# 04_CPU02.net
KiCad netlist of a schematic drawn in Altium Designer
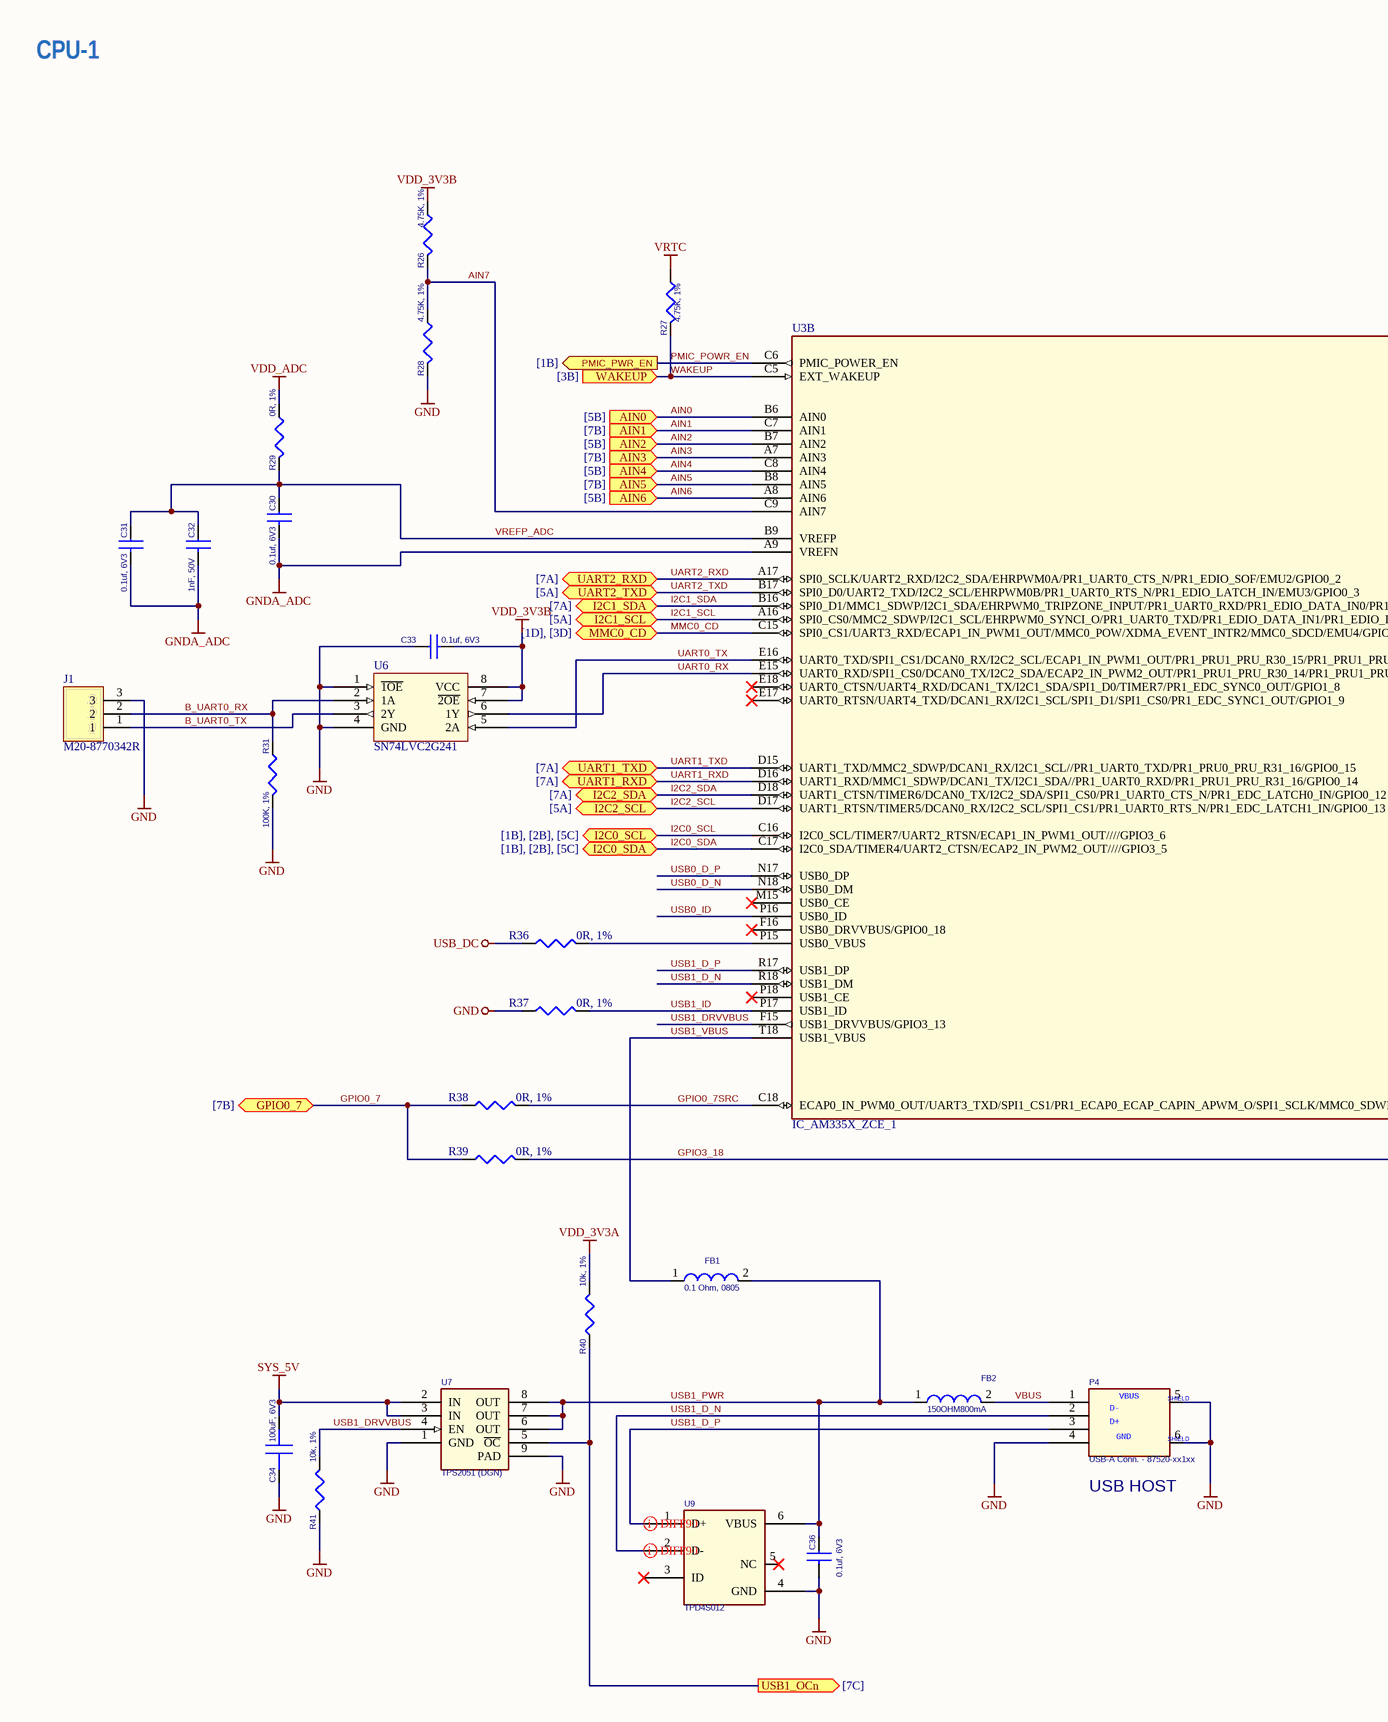
[diagram p0: 04_CPU02.SchDoc, left]
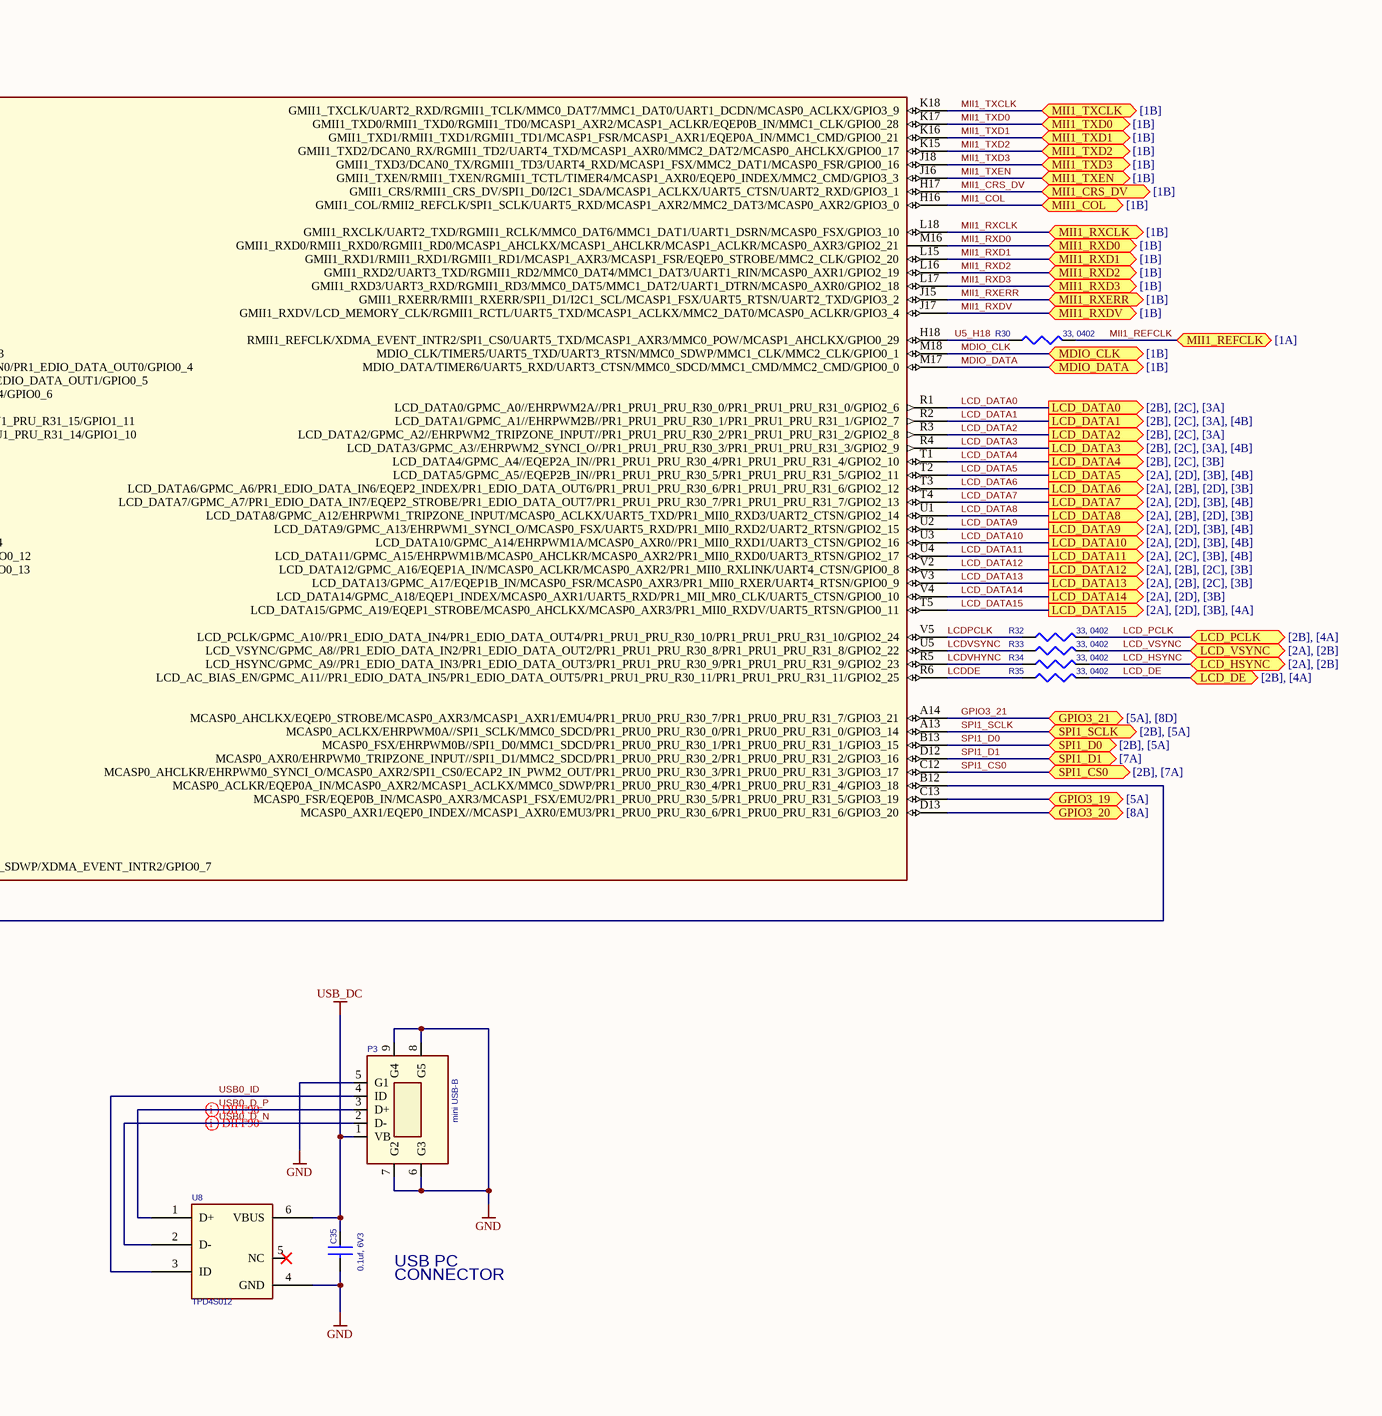
[diagram p1: 04_CPU02.SchDoc, right]

(export (version "E")
  (design (tool "Eeschema 10.0.6"))
  (components
    (comp (ref "C30")
      (value "0.1uf, 6V3")
      (footprint "402")
      (description "CAP CER 0.1UF 6.3V 10% X5R 0402")
      (fields
        (field (name "MANUFACTURER") "TDK Corporation")
        (field (name "MANUFACTURER PART NUMBER") "C1005X5R0J104K050BA")
      )
      (libsource (lib "BEAGLEBONEBLACK_REV A5B") (part "CAP_0.1uF_X7R_16V_10% 0402"))
    )
    (comp (ref "C31")
      (value "0.1uf, 6V3")
      (footprint "402")
      (description "CAP CER 0.1UF 6.3V 10% X5R 0402")
      (fields
        (field (name "MANUFACTURER") "TDK Corporation")
        (field (name "MANUFACTURER PART NUMBER") "C1005X5R0J104K050BA")
      )
      (libsource (lib "BEAGLEBONEBLACK_REV A5B") (part "CAP_0.1uF_X7R_16V_10% 0402"))
    )
    (comp (ref "C32")
      (value "1nF, 50V")
      (footprint "402")
      (description "CAP CER 1000PF 16V 10% X7R 0402")
      (fields
        (field (name "MANUFACTURER") "Yageo")
        (field (name "MANUFACTURER PART NUMBER") "CC0402KRX7R7BB102")
      )
      (libsource (lib "BEAGLEBONEBLACK_REV A5B") (part "CAP_0.001_X7R_50V_5%_0402"))
    )
    (comp (ref "C33")
      (value "0.1uf, 6V3")
      (footprint "402")
      (description "CAP CER 0.1UF 6.3V 10% X5R 0402")
      (fields
        (field (name "MANUFACTURER") "TDK Corporation")
        (field (name "MANUFACTURER PART NUMBER") "C1005X5R0J104K050BA")
      )
      (libsource (lib "BEAGLEBONEBLACK_REV A5B") (part "CAP_0.1uF_X7R_16V_10% 0402"))
    )
    (comp (ref "C34")
      (value "100uF, 6V3")
      (footprint "RD205SMD_250D")
      (description "CAP ALUM 100UF 6.3V 20% SMD")
      (fields
        (field (name "MANUFACTURER") "Cornell Dubilier Electronics (CDE)")
        (field (name "MANUFACTURER PART NUMBER") "AVE107M06D16T-F")
      )
      (libsource (lib "BEAGLEBONEBLACK_REV A5B") (part "CAP SMD"))
    )
    (comp (ref "C35")
      (value "0.1uf, 6V3")
      (footprint "402")
      (description "CAP CER 0.1UF 6.3V 10% X5R 0402")
      (fields
        (field (name "MANUFACTURER") "TDK Corporation")
        (field (name "MANUFACTURER PART NUMBER") "C1005X5R0J104K050BA")
      )
      (libsource (lib "BEAGLEBONEBLACK_REV A5B") (part "CAP_0.1uF_X7R_16V_10% 0402"))
    )
    (comp (ref "C36")
      (value "0.1uf, 6V3")
      (footprint "402")
      (description "CAP CER 0.1UF 6.3V 10% X5R 0402")
      (fields
        (field (name "MANUFACTURER") "TDK Corporation")
        (field (name "MANUFACTURER PART NUMBER") "C1005X5R0J104K050BA")
      )
      (libsource (lib "BEAGLEBONEBLACK_REV A5B") (part "CAP_0.1uF_X7R_16V_10% 0402"))
    )
    (comp (ref "FB1")
      (value "0.1 Ohm, 0805")
      (footprint "SM-7351-IND-0805")
      (description "RES .10 OHM 1/8W 5% 0805")
      (fields
        (field (name "MANUFACTURER") "CTS Resistor Products")
        (field (name "MANUFACTURER PART NUMBER") "73L3R10J")
      )
      (libsource (lib "BEAGLEBONEBLACK_REV A5B") (part "FER_180_200_0"))
    )
    (comp (ref "FB2")
      (value "150OHM800mA")
      (footprint "SM-7351-IND-0805")
      (description "FERRITE 800MA 150 OHM 0805 SMD")
      (fields (field (name "MFR") "Steward") (field (name "TIINTPARTNUMBER") "1L0010"))
      (libsource (lib "BEAGLEBONEBLACK_REV A5B") (part "FER_180_200_0"))
    )
    (comp (ref "J1")
      (value "M20-8770342R")
      (footprint "HARWIN_M20-8770342R")
      (description "Connector Header Surface Mount 3 position 0.100 (2.54mm)")
      (fields (field (name "MF") "Harwin Inc."))
      (libsource (lib "BEAGLEBONEBLACK_REV A5B_1") (part "M20-8770342R"))
    )
    (comp (ref "P3")
      (value "mini USB-B")
      (footprint "USB5MINI_4SHIELDED_SMD-5")
      (description "CONN RCPT USB MINI B R/A SMD")
      (fields (field (name "MANUFACTURER") "KYCON") (field (name "MANUFACTURER PART NUMBER") "0565790576"))
      (libsource (lib "BEAGLEBONEBLACK_REV A5B") (part "MINI-USB-AB-SOCKET"))
    )
    (comp (ref "P4")
      (value "USB-A Conn. - 87520-xx1xx")
      (description "CONN RCPT USB TYPE A R/A PCB")
      (fields (field (name "MANUFACTURER") "FCI") (field (name "MANUFACTURER PART NUMBER") "87520-0010BLF"))
      (libsource (lib "BEAGLEBONEBLACK_REV A5B") (part "CONN_54819-0578_2"))
    )
    (comp (ref "R26")
      (value "4.75K, 1%")
      (footprint "402")
      (description "RES 4.75K OHM 1/16W 1% 0402 SMD")
      (fields
        (field (name "MANUFACTURER") "Stackpole Electronics Inc")
        (field (name "MANUFACTURER PART NUMBER") "RMCF0402FT4K75")
      )
      (libsource (lib "BEAGLEBONEBLACK_REV A5B") (part "RES_4.75K_1/16W_1%_0402"))
    )
    (comp (ref "R27")
      (value "4.75K, 1%")
      (footprint "402")
      (description "RES 4.75K OHM 1/16W 1% 0402 SMD")
      (fields
        (field (name "MANUFACTURER") "Stackpole Electronics Inc")
        (field (name "MANUFACTURER PART NUMBER") "RMCF0402FT4K75")
      )
      (libsource (lib "BEAGLEBONEBLACK_REV A5B") (part "RES_4.75K_1/16W_1%_0402"))
    )
    (comp (ref "R28")
      (value "4.75K, 1%")
      (footprint "402")
      (description "RES 4.75K OHM 1/16W 1% 0402 SMD")
      (fields
        (field (name "MANUFACTURER") "Stackpole Electronics Inc")
        (field (name "MANUFACTURER PART NUMBER") "RMCF0402FT4K75")
      )
      (libsource (lib "BEAGLEBONEBLACK_REV A5B") (part "RES_4.75K_1/16W_1%_0402"))
    )
    (comp (ref "R29")
      (value "0R, 1%")
      (footprint "402")
      (description "RES 0.0 OHM 1/16W 0402 SMD")
      (fields
        (field (name "MANUFACTURER") "Yageo")
        (field (name "MANUFACTURER PART NUMBER") "RC0402JR-070RL")
      )
      (libsource (lib "BEAGLEBONEBLACK_REV A5B") (part "RES_0_1/16W_1%_0402"))
    )
    (comp (ref "R30")
      (value "33, 0402")
      (footprint "402")
      (description "RES 33 OHM 1/16W 5% 0402 SMD")
      (fields
        (field (name "MANUFACTURER") "Panasonic Electronic Components")
        (field (name "MANUFACTURER PART NUMBER") "ERJ-2GEJ330X")
      )
      (libsource (lib "BEAGLEBONEBLACK_REV A5B") (part "RES_33_0402"))
    )
    (comp (ref "R31")
      (value "100K, 1%")
      (footprint "402")
      (description "RES 100K OHM 1/16W 1% 0402 SMD")
      (fields
        (field (name "MANUFACTURER") "Stackpole Electronics Inc")
        (field (name "MANUFACTURER PART NUMBER") "RMCF0402FT100K")
      )
      (libsource (lib "BEAGLEBONEBLACK_REV A5B") (part "RES_100K_1/16W_1%_0402"))
    )
    (comp (ref "R32")
      (value "33, 0402")
      (footprint "402")
      (description "RES 33 OHM 1/16W 5% 0402 SMD")
      (fields
        (field (name "MANUFACTURER") "Panasonic Electronic Components")
        (field (name "MANUFACTURER PART NUMBER") "ERJ-2GEJ330X")
      )
      (libsource (lib "BEAGLEBONEBLACK_REV A5B") (part "RES_33_0402"))
    )
    (comp (ref "R33")
      (value "33, 0402")
      (footprint "402")
      (description "RES 33 OHM 1/16W 5% 0402 SMD")
      (fields
        (field (name "MANUFACTURER") "Panasonic Electronic Components")
        (field (name "MANUFACTURER PART NUMBER") "ERJ-2GEJ330X")
      )
      (libsource (lib "BEAGLEBONEBLACK_REV A5B") (part "RES_33_0402"))
    )
    (comp (ref "R34")
      (value "33, 0402")
      (footprint "402")
      (description "RES 33 OHM 1/16W 5% 0402 SMD")
      (fields
        (field (name "MANUFACTURER") "Panasonic Electronic Components")
        (field (name "MANUFACTURER PART NUMBER") "ERJ-2GEJ330X")
      )
      (libsource (lib "BEAGLEBONEBLACK_REV A5B") (part "RES_33_0402"))
    )
    (comp (ref "R35")
      (value "33, 0402")
      (footprint "402")
      (description "RES 33 OHM 1/16W 5% 0402 SMD")
      (fields
        (field (name "MANUFACTURER") "Panasonic Electronic Components")
        (field (name "MANUFACTURER PART NUMBER") "ERJ-2GEJ330X")
      )
      (libsource (lib "BEAGLEBONEBLACK_REV A5B") (part "RES_33_0402"))
    )
    (comp (ref "R36")
      (value "0R, 1%")
      (footprint "402")
      (description "RES 0.0 OHM 1/16W 0402 SMD")
      (fields
        (field (name "MANUFACTURER") "Yageo")
        (field (name "MANUFACTURER PART NUMBER") "RC0402JR-070RL")
      )
      (libsource (lib "BEAGLEBONEBLACK_REV A5B") (part "RES_0_1/16W_1%_0402"))
    )
    (comp (ref "R37")
      (value "0R, 1%")
      (footprint "402")
      (description "RES 0.0 OHM 1/16W 0402 SMD")
      (fields
        (field (name "MANUFACTURER") "Yageo")
        (field (name "MANUFACTURER PART NUMBER") "RC0402JR-070RL")
      )
      (libsource (lib "BEAGLEBONEBLACK_REV A5B") (part "RES_0_1/16W_1%_0402"))
    )
    (comp (ref "R38")
      (value "0R, 1%")
      (footprint "402")
      (description "RES 0.0 OHM 1/16W 0402 SMD")
      (fields
        (field (name "MANUFACTURER") "Yageo")
        (field (name "MANUFACTURER PART NUMBER") "RC0402JR-070RL")
      )
      (libsource (lib "BEAGLEBONEBLACK_REV A5B") (part "RES_0_1/16W_1%_0402"))
    )
    (comp (ref "R39")
      (value "0R, 1%")
      (footprint "402")
      (description "RES 0.0 OHM 1/16W 0402 SMD")
      (fields
        (field (name "MANUFACTURER") "Yageo")
        (field (name "MANUFACTURER PART NUMBER") "RC0402JR-070RL")
      )
      (libsource (lib "BEAGLEBONEBLACK_REV A5B") (part "RES_0_1/16W_1%_0402"))
    )
    (comp (ref "R40")
      (value "10k, 1%")
      (footprint "402")
      (description "RES 10K OHM 1/16W 5% 0402 SMD")
      (fields
        (field (name "MANUFACTURER") "Rohm Semiconductor")
        (field (name "MANUFACTURER PART NUMBER") "MCR01MZPJ103")
      )
      (libsource (lib "BEAGLEBONEBLACK_REV A5B") (part "RES SMD"))
    )
    (comp (ref "R41")
      (value "10k, 1%")
      (footprint "402")
      (description "RES 10K OHM 1/16W 5% 0402 SMD")
      (fields
        (field (name "MANUFACTURER") "Rohm Semiconductor")
        (field (name "MANUFACTURER PART NUMBER") "MCR01MZPJ103")
      )
      (libsource (lib "BEAGLEBONEBLACK_REV A5B") (part "RES SMD"))
    )
    (comp (ref "U3")
      (value "IC_AM335X_ZCE_1")
      (footprint "am33xx_15x15")
      (description "SubArctic Cortex A8 Processor 15x15")
      (fields
        (field (name "MANUFACTURER") "Texas Instruments")
        (field (name "MANUFACTURER PART NUMBER") "XAM3359ZCZ")
      )
      (libsource (lib "BEAGLEBONEBLACK_REV A5B_1") (part "IC_AM335X_ZCE_1"))
    )
    (comp (ref "U6")
      (value "SN74LVC2G241")
      (footprint "U_8_DCU")
      (description "IC BUFF/DVR TRI-ST DL 8VSSOP")
      (fields
        (field (name "MANUFACTURER") "Texas Instruments")
        (field (name "MANUFACTURER PART NUMBER") "SN74LVC2G241DCUR")
      )
      (libsource (lib "BEAGLEBONEBLACK_REV A5B") (part "SN74LVC2G241"))
    )
    (comp (ref "U7")
      (value "TPS2051 (DGN)")
      (description "IC 1.5A PWR DIST SWITCH 8-SOIC")
      (fields
        (field (name "MANUFACTURER") "Texas Instruments")
        (field (name "MANUFACTURER PART NUMBER") "TPS2051BDGNR")
      )
      (libsource (lib "BEAGLEBONEBLACK_REV A5B") (part "TPS2061_0"))
    )
    (comp (ref "U8")
      (value "TPD4S012")
      (footprint "U_6_DRY")
      (description "ESD 4channel USB Interface")
      (fields (field (name "MFR") "TI") (field (name "TIINTPARTNUMBER") "1A0233"))
      (libsource (lib "BEAGLEBONEBLACK_REV A5B") (part "PROT_TPD4S012"))
    )
    (comp (ref "U9")
      (value "TPD4S012")
      (footprint "U_6_DRY")
      (description "ESD 4channel USB Interface")
      (fields (field (name "MFR") "TI") (field (name "TIINTPARTNUMBER") "1A0233"))
      (libsource (lib "BEAGLEBONEBLACK_REV A5B") (part "PROT_TPD4S012"))
    )
  )
  (nets
    (net (code "1") (name "/AIN0") (class "Default")
      (node (ref "U3") (pin "B6") (pinfunction "AIN0_B6") (pintype "passive"))
    )
    (net (code "2") (name "/AIN1") (class "Default")
      (node (ref "U3") (pin "C7") (pinfunction "AIN1_C7") (pintype "passive"))
    )
    (net (code "3") (name "/AIN2") (class "Default")
      (node (ref "U3") (pin "B7") (pinfunction "AIN2_B7") (pintype "passive"))
    )
    (net (code "4") (name "/AIN3") (class "Default")
      (node (ref "U3") (pin "A7") (pinfunction "AIN3_A7") (pintype "passive"))
    )
    (net (code "5") (name "/AIN4") (class "Default")
      (node (ref "U3") (pin "C8") (pinfunction "AIN4_C8") (pintype "passive"))
    )
    (net (code "6") (name "/AIN5") (class "Default")
      (node (ref "U3") (pin "B8") (pinfunction "AIN5_B8") (pintype "passive"))
    )
    (net (code "7") (name "/AIN6") (class "Default")
      (node (ref "U3") (pin "A8") (pinfunction "AIN6_A8") (pintype "passive"))
    )
    (net (code "8") (name "/AIN7") (class "Default")
      (node (ref "R26") (pin "2") (pinfunction "2_2") (pintype "passive"))
      (node (ref "R28") (pin "1") (pinfunction "1_1") (pintype "passive"))
      (node (ref "U3") (pin "C9") (pinfunction "AIN7_C9") (pintype "passive"))
    )
    (net (code "9") (name "/B_UART0_RX") (class "Default")
      (node (ref "J1") (pin "2") (pinfunction "2_2") (pintype "passive"))
      (node (ref "R31") (pin "1") (pinfunction "1_1") (pintype "passive"))
      (node (ref "U6") (pin "2") (pinfunction "1A_2") (pintype "input"))
    )
    (net (code "10") (name "/B_UART0_TX") (class "Default")
      (node (ref "J1") (pin "1") (pinfunction "1_1") (pintype "passive"))
      (node (ref "U6") (pin "3") (pinfunction "2Y_3") (pintype "output"))
    )
    (net (code "11") (name "/GPIO0_7") (class "Default")
      (node (ref "R38") (pin "1") (pinfunction "1_1") (pintype "passive"))
      (node (ref "R39") (pin "1") (pinfunction "1_1") (pintype "passive"))
    )
    (net (code "12") (name "/GPIO0_7SRC") (class "Default")
      (node (ref "R38") (pin "2") (pinfunction "2_2") (pintype "passive"))
      (node (ref "U3") (pin "C18") (pinfunction "ECAP0_IN_PWM0_OUT/UART3_TXD/SPI1_CS1/PR1_ECAP0_ECAP_CAPIN_APWM_O/SPI1_SCLK/MMC0_SDWP/XDMA_EVENT_INTR2/GPIO0_7_C18") (pintype "bidirectional"))
    )
    (net (code "13") (name "/GPIO3_18") (class "Default")
      (node (ref "R39") (pin "2") (pinfunction "2_2") (pintype "passive"))
      (node (ref "U3") (pin "B12") (pinfunction "MCASP0_ACLKR/EQEP0A_IN/MCASP0_AXR2/MCASP1_ACLKX/MMC0_SDWP/PR1_PRU0_PRU_R30_4/PR1_PRU0_PRU_R31_4/GPIO3_18_B12") (pintype "bidirectional"))
    )
    (net (code "14") (name "/GPIO3_19") (class "Default")
      (node (ref "U3") (pin "C13") (pinfunction "MCASP0_FSR/EQEP0B_IN/MCASP0_AXR3/MCASP1_FSX/EMU2/PR1_PRU0_PRU_R30_5/PR1_PRU0_PRU_R31_5/GPIO3_19_C13") (pintype "bidirectional"))
    )
    (net (code "15") (name "/GPIO3_20") (class "Default")
      (node (ref "U3") (pin "D13") (pinfunction "MCASP0_AXR1/EQEP0_INDEX//MCASP1_AXR0/EMU3/PR1_PRU0_PRU_R30_6/PR1_PRU0_PRU_R31_6/GPIO3_20_D13") (pintype "bidirectional"))
    )
    (net (code "16") (name "/GPIO3_21") (class "Default")
      (node (ref "U3") (pin "A14") (pinfunction "MCASP0_AHCLKX/EQEP0_STROBE/MCASP0_AXR3/MCASP1_AXR1/EMU4/PR1_PRU0_PRU_R30_7/PR1_PRU0_PRU_R31_7/GPIO3_21_A14") (pintype "bidirectional"))
    )
    (net (code "17") (name "/I2C0_SCL") (class "Default")
      (node (ref "U3") (pin "C16") (pinfunction "I2C0_SCL/TIMER7/UART2_RTSN/ECAP1_IN_PWM1_OUT////GPIO3_6_C16") (pintype "bidirectional"))
    )
    (net (code "18") (name "/I2C0_SDA") (class "Default")
      (node (ref "U3") (pin "C17") (pinfunction "I2C0_SDA/TIMER4/UART2_CTSN/ECAP2_IN_PWM2_OUT////GPIO3_5_C17") (pintype "bidirectional"))
    )
    (net (code "19") (name "/I2C1_SCL") (class "Default")
      (node (ref "U3") (pin "A16") (pinfunction "SPI0_CS0/MMC2_SDWP/I2C1_SCL/EHRPWM0_SYNCI_O/PR1_UART0_TXD/PR1_EDIO_DATA_IN1/PR1_EDIO_DATA_OUT1/GPIO0_5_A16") (pintype "bidirectional"))
    )
    (net (code "20") (name "/I2C1_SDA") (class "Default")
      (node (ref "U3") (pin "B16") (pinfunction "SPI0_D1/MMC1_SDWP/I2C1_SDA/EHRPWM0_TRIPZONE_INPUT/PR1_UART0_RXD/PR1_EDIO_DATA_IN0/PR1_EDIO_DATA_OUT0/GPIO0_4_B16") (pintype "bidirectional"))
    )
    (net (code "21") (name "/I2C2_SCL") (class "Default")
      (node (ref "U3") (pin "D17") (pinfunction "UART1_RTSN/TIMER5/DCAN0_RX/I2C2_SCL/SPI1_CS1/PR1_UART0_RTS_N/PR1_EDC_LATCH1_IN/GPIO0_13_D17") (pintype "bidirectional"))
    )
    (net (code "22") (name "/I2C2_SDA") (class "Default")
      (node (ref "U3") (pin "D18") (pinfunction "UART1_CTSN/TIMER6/DCAN0_TX/I2C2_SDA/SPI1_CS0/PR1_UART0_CTS_N/PR1_EDC_LATCH0_IN/GPIO0_12_D18") (pintype "bidirectional"))
    )
    (net (code "23") (name "/LCDDE") (class "Default")
      (node (ref "R35") (pin "1") (pinfunction "1_1") (pintype "passive"))
      (node (ref "U3") (pin "R6") (pinfunction "LCD_AC_BIAS_EN/GPMC_A11//PR1_EDIO_DATA_IN5/PR1_EDIO_DATA_OUT5/PR1_PRU1_PRU_R30_11/PR1_PRU1_PRU_R31_11/GPIO2_25_R6") (pintype "bidirectional"))
    )
    (net (code "24") (name "/LCDPCLK") (class "Default")
      (node (ref "R32") (pin "1") (pinfunction "1_1") (pintype "passive"))
      (node (ref "U3") (pin "V5") (pinfunction "LCD_PCLK/GPMC_A10//PR1_EDIO_DATA_IN4/PR1_EDIO_DATA_OUT4/PR1_PRU1_PRU_R30_10/PR1_PRU1_PRU_R31_10/GPIO2_24_V5") (pintype "bidirectional"))
    )
    (net (code "25") (name "/LCDVHYNC") (class "Default")
      (node (ref "R34") (pin "1") (pinfunction "1_1") (pintype "passive"))
      (node (ref "U3") (pin "R5") (pinfunction "LCD_HSYNC/GPMC_A9//PR1_EDIO_DATA_IN3/PR1_EDIO_DATA_OUT3/PR1_PRU1_PRU_R30_9/PR1_PRU1_PRU_R31_9/GPIO2_23_R5") (pintype "bidirectional"))
    )
    (net (code "26") (name "/LCDVSYNC") (class "Default")
      (node (ref "R33") (pin "1") (pinfunction "1_1") (pintype "passive"))
      (node (ref "U3") (pin "U5") (pinfunction "LCD_VSYNC/GPMC_A8//PR1_EDIO_DATA_IN2/PR1_EDIO_DATA_OUT2/PR1_PRU1_PRU_R30_8/PR1_PRU1_PRU_R31_8/GPIO2_22_U5") (pintype "bidirectional"))
    )
    (net (code "27") (name "/LCD_DATA0") (class "Default")
      (node (ref "U3") (pin "R1") (pinfunction "LCD_DATA0/GPMC_A0//EHRPWM2A//PR1_PRU1_PRU_R30_0/PR1_PRU1_PRU_R31_0/GPIO2_6_R1") (pintype "output"))
    )
    (net (code "28") (name "/LCD_DATA1") (class "Default")
      (node (ref "U3") (pin "R2") (pinfunction "LCD_DATA1/GPMC_A1//EHRPWM2B//PR1_PRU1_PRU_R30_1/PR1_PRU1_PRU_R31_1/GPIO2_7_R2") (pintype "output"))
    )
    (net (code "29") (name "/LCD_DATA2") (class "Default")
      (node (ref "U3") (pin "R3") (pinfunction "LCD_DATA2/GPMC_A2//EHRPWM2_TRIPZONE_INPUT//PR1_PRU1_PRU_R30_2/PR1_PRU1_PRU_R31_2/GPIO2_8_R3") (pintype "output"))
    )
    (net (code "30") (name "/LCD_DATA3") (class "Default")
      (node (ref "U3") (pin "R4") (pinfunction "LCD_DATA3/GPMC_A3//EHRPWM2_SYNCI_O//PR1_PRU1_PRU_R30_3/PR1_PRU1_PRU_R31_3/GPIO2_9_R4") (pintype "output"))
    )
    (net (code "31") (name "/LCD_DATA4") (class "Default")
      (node (ref "U3") (pin "T1") (pinfunction "LCD_DATA4/GPMC_A4//EQEP2A_IN//PR1_PRU1_PRU_R30_4/PR1_PRU1_PRU_R31_4/GPIO2_10_T1") (pintype "bidirectional"))
    )
    (net (code "32") (name "/LCD_DATA5") (class "Default")
      (node (ref "U3") (pin "T2") (pinfunction "LCD_DATA5/GPMC_A5//EQEP2B_IN//PR1_PRU1_PRU_R30_5/PR1_PRU1_PRU_R31_5/GPIO2_11_T2") (pintype "bidirectional"))
    )
    (net (code "33") (name "/LCD_DATA6") (class "Default")
      (node (ref "U3") (pin "T3") (pinfunction "LCD_DATA6/GPMC_A6/PR1_EDIO_DATA_IN6/EQEP2_INDEX/PR1_EDIO_DATA_OUT6/PR1_PRU1_PRU_R30_6/PR1_PRU1_PRU_R31_6/GPIO2_12_T3") (pintype "bidirectional"))
    )
    (net (code "34") (name "/LCD_DATA7") (class "Default")
      (node (ref "U3") (pin "T4") (pinfunction "LCD_DATA7/GPMC_A7/PR1_EDIO_DATA_IN7/EQEP2_STROBE/PR1_EDIO_DATA_OUT7/PR1_PRU1_PRU_R30_7/PR1_PRU1_PRU_R31_7/GPIO2_13_T4") (pintype "bidirectional"))
    )
    (net (code "35") (name "/LCD_DATA8") (class "Default")
      (node (ref "U3") (pin "U1") (pinfunction "LCD_DATA8/GPMC_A12/EHRPWM1_TRIPZONE_INPUT/MCASP0_ACLKX/UART5_TXD/PR1_MII0_RXD3/UART2_CTSN/GPIO2_14_U1") (pintype "bidirectional"))
    )
    (net (code "36") (name "/LCD_DATA9") (class "Default")
      (node (ref "U3") (pin "U2") (pinfunction "LCD_DATA9/GPMC_A13/EHRPWM1_SYNCI_O/MCASP0_FSX/UART5_RXD/PR1_MII0_RXD2/UART2_RTSN/GPIO2_15_U2") (pintype "bidirectional"))
    )
    (net (code "37") (name "/LCD_DATA10") (class "Default")
      (node (ref "U3") (pin "U3") (pinfunction "LCD_DATA10/GPMC_A14/EHRPWM1A/MCASP0_AXR0//PR1_MII0_RXD1/UART3_CTSN/GPIO2_16_U3") (pintype "bidirectional"))
    )
    (net (code "38") (name "/LCD_DATA11") (class "Default")
      (node (ref "U3") (pin "U4") (pinfunction "LCD_DATA11/GPMC_A15/EHRPWM1B/MCASP0_AHCLKR/MCASP0_AXR2/PR1_MII0_RXD0/UART3_RTSN/GPIO2_17_U4") (pintype "bidirectional"))
    )
    (net (code "39") (name "/LCD_DATA12") (class "Default")
      (node (ref "U3") (pin "V2") (pinfunction "LCD_DATA12/GPMC_A16/EQEP1A_IN/MCASP0_ACLKR/MCASP0_AXR2/PR1_MII0_RXLINK/UART4_CTSN/GPIO0_8_V2") (pintype "bidirectional"))
    )
    (net (code "40") (name "/LCD_DATA13") (class "Default")
      (node (ref "U3") (pin "V3") (pinfunction "LCD_DATA13/GPMC_A17/EQEP1B_IN/MCASP0_FSR/MCASP0_AXR3/PR1_MII0_RXER/UART4_RTSN/GPIO0_9_V3") (pintype "bidirectional"))
    )
    (net (code "41") (name "/LCD_DATA14") (class "Default")
      (node (ref "U3") (pin "V4") (pinfunction "LCD_DATA14/GPMC_A18/EQEP1_INDEX/MCASP0_AXR1/UART5_RXD/PR1_MII_MR0_CLK/UART5_CTSN/GPIO0_10_V4") (pintype "bidirectional"))
    )
    (net (code "42") (name "/LCD_DATA15") (class "Default")
      (node (ref "U3") (pin "T5") (pinfunction "LCD_DATA15/GPMC_A19/EQEP1_STROBE/MCASP0_AHCLKX/MCASP0_AXR3/PR1_MII0_RXDV/UART5_RTSN/GPIO0_11_T5") (pintype "bidirectional"))
    )
    (net (code "43") (name "/LCD_DE") (class "Default")
      (node (ref "R35") (pin "2") (pinfunction "2_2") (pintype "passive"))
    )
    (net (code "44") (name "/LCD_HSYNC") (class "Default")
      (node (ref "R34") (pin "2") (pinfunction "2_2") (pintype "passive"))
    )
    (net (code "45") (name "/LCD_PCLK") (class "Default")
      (node (ref "R32") (pin "2") (pinfunction "2_2") (pintype "passive"))
    )
    (net (code "46") (name "/LCD_VSYNC") (class "Default")
      (node (ref "R33") (pin "2") (pinfunction "2_2") (pintype "passive"))
    )
    (net (code "47") (name "/MDIO_CLK") (class "Default")
      (node (ref "U3") (pin "M18") (pinfunction "MDIO_CLK/TIMER5/UART5_TXD/UART3_RTSN/MMC0_SDWP/MMC1_CLK/MMC2_CLK/GPIO0_1_M18") (pintype "bidirectional"))
    )
    (net (code "48") (name "/MDIO_DATA") (class "Default")
      (node (ref "U3") (pin "M17") (pinfunction "MDIO_DATA/TIMER6/UART5_RXD/UART3_CTSN/MMC0_SDCD/MMC1_CMD/MMC2_CMD/GPIO0_0_M17") (pintype "bidirectional"))
    )
    (net (code "49") (name "/MII1_COL") (class "Default")
      (node (ref "U3") (pin "H16") (pinfunction "GMII1_COL/RMII2_REFCLK/SPI1_SCLK/UART5_RXD/MCASP1_AXR2/MMC2_DAT3/MCASP0_AXR2/GPIO3_0_H16") (pintype "bidirectional"))
    )
    (net (code "50") (name "/MII1_CRS_DV") (class "Default")
      (node (ref "U3") (pin "H17") (pinfunction "GMII1_CRS/RMII1_CRS_DV/SPI1_D0/I2C1_SDA/MCASP1_ACLKX/UART5_CTSN/UART2_RXD/GPIO3_1_H17") (pintype "bidirectional"))
    )
    (net (code "51") (name "/MII1_REFCLK") (class "Default")
      (node (ref "R30") (pin "2") (pinfunction "2_2") (pintype "passive"))
    )
    (net (code "52") (name "/MII1_RXCLK") (class "Default")
      (node (ref "U3") (pin "L18") (pinfunction "GMII1_RXCLK/UART2_TXD/RGMII1_RCLK/MMC0_DAT6/MMC1_DAT1/UART1_DSRN/MCASP0_FSX/GPIO3_10_L18") (pintype "bidirectional"))
    )
    (net (code "53") (name "/MII1_RXD0") (class "Default")
      (node (ref "U3") (pin "M16") (pinfunction "GMII1_RXD0/RMII1_RXD0/RGMII1_RD0/MCASP1_AHCLKX/MCASP1_AHCLKR/MCASP1_ACLKR/MCASP0_AXR3/GPIO2_21_M16") (pintype "passive"))
    )
    (net (code "54") (name "/MII1_RXD1") (class "Default")
      (node (ref "U3") (pin "L15") (pinfunction "GMII1_RXD1/RMII1_RXD1/RGMII1_RD1/MCASP1_AXR3/MCASP1_FSR/EQEP0_STROBE/MMC2_CLK/GPIO2_20_L15") (pintype "bidirectional"))
    )
    (net (code "55") (name "/MII1_RXD2") (class "Default")
      (node (ref "U3") (pin "L16") (pinfunction "GMII1_RXD2/UART3_TXD/RGMII1_RD2/MMC0_DAT4/MMC1_DAT3/UART1_RIN/MCASP0_AXR1/GPIO2_19_L16") (pintype "bidirectional"))
    )
    (net (code "56") (name "/MII1_RXD3") (class "Default")
      (node (ref "U3") (pin "L17") (pinfunction "GMII1_RXD3/UART3_RXD/RGMII1_RD3/MMC0_DAT5/MMC1_DAT2/UART1_DTRN/MCASP0_AXR0/GPIO2_18_L17") (pintype "bidirectional"))
    )
    (net (code "57") (name "/MII1_RXDV") (class "Default")
      (node (ref "U3") (pin "J17") (pinfunction "GMII1_RXDV/LCD_MEMORY_CLK/RGMII1_RCTL/UART5_TXD/MCASP1_ACLKX/MMC2_DAT0/MCASP0_ACLKR/GPIO3_4_J17") (pintype "bidirectional"))
    )
    (net (code "58") (name "/MII1_RXERR") (class "Default")
      (node (ref "U3") (pin "J15") (pinfunction "GMII1_RXERR/RMII1_RXERR/SPI1_D1/I2C1_SCL/MCASP1_FSX/UART5_RTSN/UART2_TXD/GPIO3_2_J15") (pintype "bidirectional"))
    )
    (net (code "59") (name "/MII1_TXCLK") (class "Default")
      (node (ref "U3") (pin "K18") (pinfunction "GMII1_TXCLK/UART2_RXD/RGMII1_TCLK/MMC0_DAT7/MMC1_DAT0/UART1_DCDN/MCASP0_ACLKX/GPIO3_9_K18") (pintype "bidirectional"))
    )
    (net (code "60") (name "/MII1_TXD0") (class "Default")
      (node (ref "U3") (pin "K17") (pinfunction "GMII1_TXD0/RMII1_TXD0/RGMII1_TD0/MCASP1_AXR2/MCASP1_ACLKR/EQEP0B_IN/MMC1_CLK/GPIO0_28_K17") (pintype "bidirectional"))
    )
    (net (code "61") (name "/MII1_TXD1") (class "Default")
      (node (ref "U3") (pin "K16") (pinfunction "GMII1_TXD1/RMII1_TXD1/RGMII1_TD1/MCASP1_FSR/MCASP1_AXR1/EQEP0A_IN/MMC1_CMD/GPIO0_21_K16") (pintype "bidirectional"))
    )
    (net (code "62") (name "/MII1_TXD2") (class "Default")
      (node (ref "U3") (pin "K15") (pinfunction "GMII1_TXD2/DCAN0_RX/RGMII1_TD2/UART4_TXD/MCASP1_AXR0/MMC2_DAT2/MCASP0_AHCLKX/GPIO0_17_K15") (pintype "bidirectional"))
    )
    (net (code "63") (name "/MII1_TXD3") (class "Default")
      (node (ref "U3") (pin "J18") (pinfunction "GMII1_TXD3/DCAN0_TX/RGMII1_TD3/UART4_RXD/MCASP1_FSX/MMC2_DAT1/MCASP0_FSR/GPIO0_16_J18") (pintype "bidirectional"))
    )
    (net (code "64") (name "/MII1_TXEN") (class "Default")
      (node (ref "U3") (pin "J16") (pinfunction "GMII1_TXEN/RMII1_TXEN/RGMII1_TCTL/TIMER4/MCASP1_AXR0/EQEP0_INDEX/MMC2_CMD/GPIO3_3_J16") (pintype "bidirectional"))
    )
    (net (code "65") (name "/MMC0_CD") (class "Default")
      (node (ref "U3") (pin "C15") (pinfunction "SPI0_CS1/UART3_RXD/ECAP1_IN_PWM1_OUT/MMC0_POW/XDMA_EVENT_INTR2/MMC0_SDCD/EMU4/GPIO0_6_C15") (pintype "bidirectional"))
    )
    (net (code "66") (name "/PMIC_POWR_EN") (class "Default")
      (node (ref "R27") (pin "2") (pinfunction "2_2") (pintype "passive"))
      (node (ref "U3") (pin "C5") (pinfunction "EXT_WAKEUP_C5") (pintype "input"))
      (node (ref "U3") (pin "C6") (pinfunction "PMIC_POWER_EN_C6") (pintype "output"))
    )
    (net (code "67") (name "/SPI1_CS0") (class "Default")
      (node (ref "U3") (pin "C12") (pinfunction "MCASP0_AHCLKR/EHRPWM0_SYNCI_O/MCASP0_AXR2/SPI1_CS0/ECAP2_IN_PWM2_OUT/PR1_PRU0_PRU_R30_3/PR1_PRU0_PRU_R31_3/GPIO3_17_C12") (pintype "bidirectional"))
    )
    (net (code "68") (name "/SPI1_D0") (class "Default")
      (node (ref "U3") (pin "B13") (pinfunction "MCASP0_FSX/EHRPWM0B//SPI1_D0/MMC1_SDCD/PR1_PRU0_PRU_R30_1/PR1_PRU0_PRU_R31_1/GPIO3_15_B13") (pintype "bidirectional"))
    )
    (net (code "69") (name "/SPI1_D1") (class "Default")
      (node (ref "U3") (pin "D12") (pinfunction "MCASP0_AXR0/EHRPWM0_TRIPZONE_INPUT//SPI1_D1/MMC2_SDCD/PR1_PRU0_PRU_R30_2/PR1_PRU0_PRU_R31_2/GPIO3_16_D12") (pintype "bidirectional"))
    )
    (net (code "70") (name "/SPI1_SCLK") (class "Default")
      (node (ref "U3") (pin "A13") (pinfunction "MCASP0_ACLKX/EHRPWM0A//SPI1_SCLK/MMC0_SDCD/PR1_PRU0_PRU_R30_0/PR1_PRU0_PRU_R31_0/GPIO3_14_A13") (pintype "bidirectional"))
    )
    (net (code "71") (name "/U5_H18") (class "Default")
      (node (ref "R30") (pin "1") (pinfunction "1_1") (pintype "passive"))
      (node (ref "U3") (pin "H18") (pinfunction "RMII1_REFCLK/XDMA_EVENT_INTR2/SPI1_CS0/UART5_TXD/MCASP1_AXR3/MMC0_POW/MCASP1_AHCLKX/GPIO0_29_H18") (pintype "bidirectional"))
    )
    (net (code "72") (name "/UART0_RX") (class "Default")
      (node (ref "U3") (pin "E15") (pinfunction "UART0_RXD/SPI1_CS0/DCAN0_TX/I2C2_SDA/ECAP2_IN_PWM2_OUT/PR1_PRU1_PRU_R30_14/PR1_PRU1_PRU_R31_14/GPIO1_10_E15") (pintype "bidirectional"))
      (node (ref "U6") (pin "6") (pinfunction "1Y_6") (pintype "output"))
    )
    (net (code "73") (name "/UART0_TX") (class "Default")
      (node (ref "U3") (pin "E16") (pinfunction "UART0_TXD/SPI1_CS1/DCAN0_RX/I2C2_SCL/ECAP1_IN_PWM1_OUT/PR1_PRU1_PRU_R30_15/PR1_PRU1_PRU_R31_15/GPIO1_11_E16") (pintype "bidirectional"))
      (node (ref "U6") (pin "5") (pinfunction "2A_5") (pintype "input"))
    )
    (net (code "74") (name "/UART1_RXD") (class "Default")
      (node (ref "U3") (pin "D16") (pinfunction "UART1_RXD/MMC1_SDWP/DCAN1_TX/I2C1_SDA//PR1_UART0_RXD/PR1_PRU1_PRU_R31_16/GPIO0_14_D16") (pintype "bidirectional"))
    )
    (net (code "75") (name "/UART1_TXD") (class "Default")
      (node (ref "U3") (pin "D15") (pinfunction "UART1_TXD/MMC2_SDWP/DCAN1_RX/I2C1_SCL//PR1_UART0_TXD/PR1_PRU0_PRU_R31_16/GPIO0_15_D15") (pintype "bidirectional"))
    )
    (net (code "76") (name "/UART2_RXD") (class "Default")
      (node (ref "U3") (pin "A17") (pinfunction "SPI0_SCLK/UART2_RXD/I2C2_SDA/EHRPWM0A/PR1_UART0_CTS_N/PR1_EDIO_SOF/EMU2/GPIO0_2_A17") (pintype "bidirectional"))
    )
    (net (code "77") (name "/UART2_TXD") (class "Default")
      (node (ref "U3") (pin "B17") (pinfunction "SPI0_D0/UART2_TXD/I2C2_SCL/EHRPWM0B/PR1_UART0_RTS_N/PR1_EDIO_LATCH_IN/EMU3/GPIO0_3_B17") (pintype "bidirectional"))
    )
    (net (code "78") (name "/USB0_D_N") (class "Default")
      (node (ref "P3") (pin "2") (pinfunction "D-_2") (pintype "passive"))
      (node (ref "U3") (pin "N18") (pinfunction "USB0_DM_N18") (pintype "bidirectional"))
      (node (ref "U8") (pin "2") (pinfunction "D-_2") (pintype "passive"))
    )
    (net (code "79") (name "/USB0_D_P") (class "Default")
      (node (ref "P3") (pin "3") (pinfunction "D+_3") (pintype "passive"))
      (node (ref "U3") (pin "N17") (pinfunction "USB0_DP_N17") (pintype "bidirectional"))
      (node (ref "U8") (pin "1") (pinfunction "D+_1") (pintype "passive"))
    )
    (net (code "80") (name "/USB0_ID") (class "Default")
      (node (ref "P3") (pin "4") (pinfunction "ID_4") (pintype "passive"))
      (node (ref "U3") (pin "P16") (pinfunction "USB0_ID_P16") (pintype "passive"))
      (node (ref "U8") (pin "3") (pinfunction "ID_3") (pintype "passive"))
    )
    (net (code "81") (name "/USB1_DRVVBUS") (class "Default")
      (node (ref "R41") (pin "1") (pinfunction "P1_1") (pintype "passive"))
      (node (ref "U3") (pin "F15") (pinfunction "USB1_DRVVBUS/GPIO3_13_F15") (pintype "output"))
      (node (ref "U7") (pin "4") (pinfunction "EN_4") (pintype "input"))
    )
    (net (code "82") (name "/USB1_D_N") (class "Default")
      (node (ref "P4") (pin "2") (pinfunction "P2_2") (pintype "passive"))
      (node (ref "U3") (pin "R18") (pinfunction "USB1_DM_R18") (pintype "bidirectional"))
      (node (ref "U9") (pin "2") (pinfunction "D-_2") (pintype "passive"))
    )
    (net (code "83") (name "/USB1_D_P") (class "Default")
      (node (ref "P4") (pin "3") (pinfunction "P3_3") (pintype "passive"))
      (node (ref "U3") (pin "R17") (pinfunction "USB1_DP_R17") (pintype "bidirectional"))
      (node (ref "U9") (pin "1") (pinfunction "D+_1") (pintype "passive"))
    )
    (net (code "84") (name "/USB1_ID") (class "Default")
      (node (ref "R37") (pin "2") (pinfunction "2_2") (pintype "passive"))
      (node (ref "U3") (pin "P17") (pinfunction "USB1_ID_P17") (pintype "passive"))
    )
    (net (code "85") (name "/USB1_OCn") (class "Default")
      (node (ref "R40") (pin "2") (pinfunction "P2_2") (pintype "passive"))
      (node (ref "U7") (pin "5") (pinfunction "~{OC}_5") (pintype "passive"))
    )
    (net (code "86") (name "/USB1_PWR") (class "Default")
      (node (ref "C36") (pin "1") (pinfunction "1_1") (pintype "passive"))
      (node (ref "FB1") (pin "2") (pinfunction "2_2") (pintype "passive"))
      (node (ref "FB2") (pin "1") (pinfunction "1_1") (pintype "passive"))
      (node (ref "U7") (pin "6") (pinfunction "OUT_6") (pintype "power_in"))
      (node (ref "U7") (pin "7") (pinfunction "OUT_7") (pintype "power_in"))
      (node (ref "U7") (pin "8") (pinfunction "OUT_8") (pintype "power_in"))
      (node (ref "U9") (pin "6") (pinfunction "VBUS_6") (pintype "power_in"))
    )
    (net (code "87") (name "/USB1_VBUS") (class "Default")
      (node (ref "FB1") (pin "1") (pinfunction "1_1") (pintype "passive"))
      (node (ref "U3") (pin "T18") (pinfunction "USB1_VBUS_T18") (pintype "passive"))
    )
    (net (code "88") (name "/VBUS") (class "Default")
      (node (ref "FB2") (pin "2") (pinfunction "2_2") (pintype "passive"))
      (node (ref "P4") (pin "1") (pinfunction "P1_1") (pintype "passive"))
    )
    (net (code "89") (name "/VREFP_ADC") (class "Default")
      (node (ref "C30") (pin "1") (pinfunction "1_1") (pintype "passive"))
      (node (ref "C31") (pin "1") (pinfunction "1_1") (pintype "passive"))
      (node (ref "C32") (pin "1") (pinfunction "1_1") (pintype "passive"))
      (node (ref "R29") (pin "2") (pinfunction "2_2") (pintype "passive"))
      (node (ref "U3") (pin "B9") (pinfunction "VREFP_B9") (pintype "passive"))
    )
    (net (code "90") (name "GND") (class "Default")
      (node (ref "C33") (pin "1") (pinfunction "1_1") (pintype "passive"))
      (node (ref "C34") (pin "2") (pinfunction "2_2") (pintype "passive"))
      (node (ref "C35") (pin "2") (pinfunction "2_2") (pintype "passive"))
      (node (ref "C36") (pin "2") (pinfunction "2_2") (pintype "passive"))
      (node (ref "J1") (pin "3") (pinfunction "3_3") (pintype "passive"))
      (node (ref "P3") (pin "5") (pinfunction "G1_5") (pintype "passive"))
      (node (ref "P3") (pin "6") (pinfunction "G3_6") (pintype "passive"))
      (node (ref "P3") (pin "7") (pinfunction "G2_7") (pintype "passive"))
      (node (ref "P3") (pin "8") (pinfunction "G5_8") (pintype "passive"))
      (node (ref "P3") (pin "9") (pinfunction "G4_9") (pintype "passive"))
      (node (ref "P4") (pin "4") (pinfunction "P4_4") (pintype "passive"))
      (node (ref "P4") (pin "5") (pinfunction "SHELD1_5") (pintype "passive"))
      (node (ref "P4") (pin "6") (pinfunction "PAD4_6") (pintype "passive"))
      (node (ref "R28") (pin "2") (pinfunction "2_2") (pintype "passive"))
      (node (ref "R31") (pin "2") (pinfunction "2_2") (pintype "passive"))
      (node (ref "R37") (pin "1") (pinfunction "1_1") (pintype "passive"))
      (node (ref "R41") (pin "2") (pinfunction "P2_2") (pintype "passive"))
      (node (ref "U6") (pin "1") (pinfunction "~{1OE}_1") (pintype "input"))
      (node (ref "U6") (pin "4") (pinfunction "GND_4") (pintype "power_in"))
      (node (ref "U7") (pin "1") (pinfunction "GND_1") (pintype "power_in"))
      (node (ref "U7") (pin "9") (pinfunction "PAD_9") (pintype "passive"))
      (node (ref "U8") (pin "4") (pinfunction "GND_4") (pintype "power_in"))
      (node (ref "U9") (pin "4") (pinfunction "GND_4") (pintype "power_in"))
    )
    (net (code "91") (name "GNDA_ADC") (class "Default")
      (node (ref "C30") (pin "2") (pinfunction "2_2") (pintype "passive"))
      (node (ref "C31") (pin "2") (pinfunction "2_2") (pintype "passive"))
      (node (ref "C32") (pin "2") (pinfunction "2_2") (pintype "passive"))
      (node (ref "U3") (pin "A9") (pinfunction "VREFN_A9") (pintype "passive"))
    )
    (net (code "92") (name "Net-(U3B-USB0_VBUS)") (class "Default")
      (node (ref "R36") (pin "2") (pinfunction "2_2") (pintype "passive"))
      (node (ref "U3") (pin "P15") (pinfunction "USB0_VBUS_P15") (pintype "passive"))
    )
    (net (code "93") (name "SYS_5V") (class "Default")
      (node (ref "C34") (pin "1") (pinfunction "1_1") (pintype "passive"))
      (node (ref "U7") (pin "2") (pinfunction "IN_2") (pintype "power_in"))
      (node (ref "U7") (pin "3") (pinfunction "IN_3") (pintype "power_in"))
    )
    (net (code "94") (name "USB_DC") (class "Default")
      (node (ref "C35") (pin "1") (pinfunction "1_1") (pintype "passive"))
      (node (ref "P3") (pin "1") (pinfunction "VB_1") (pintype "passive"))
      (node (ref "R36") (pin "1") (pinfunction "1_1") (pintype "passive"))
      (node (ref "U8") (pin "6") (pinfunction "VBUS_6") (pintype "power_in"))
    )
    (net (code "95") (name "VDD_3V3A") (class "Default")
      (node (ref "R40") (pin "1") (pinfunction "P1_1") (pintype "passive"))
    )
    (net (code "96") (name "VDD_3V3B") (class "Default")
      (node (ref "C33") (pin "2") (pinfunction "2_2") (pintype "passive"))
      (node (ref "R26") (pin "1") (pinfunction "1_1") (pintype "passive"))
      (node (ref "U6") (pin "7") (pinfunction "~{2OE}_7") (pintype "input"))
      (node (ref "U6") (pin "8") (pinfunction "VCC_8") (pintype "power_in"))
    )
    (net (code "97") (name "VDD_ADC") (class "Default")
      (node (ref "R29") (pin "1") (pinfunction "1_1") (pintype "passive"))
    )
    (net (code "98") (name "VRTC") (class "Default")
      (node (ref "R27") (pin "1") (pinfunction "1_1") (pintype "passive"))
    )
    (net (code "99") (name "unconnected-(U3B-UART0_CTSN{slash}UART4_RXD{slash}DCAN1_TX{slash}I2C1_SDA{slash}SPI1_D0{slash}TIMER7{slash}PR1_EDC_SYNC0_OUT{slash}GPIO1_8-PadE18)") (class "Default")
      (node (ref "U3") (pin "E18") (pinfunction "UART0_CTSN/UART4_RXD/DCAN1_TX/I2C1_SDA/SPI1_D0/TIMER7/PR1_EDC_SYNC0_OUT/GPIO1_8_E18") (pintype "bidirectional+no_connect"))
    )
    (net (code "100") (name "unconnected-(U3B-UART0_RTSN{slash}UART4_TXD{slash}DCAN1_RX{slash}I2C1_SCL{slash}SPI1_D1{slash}SPI1_CS0{slash}PR1_EDC_SYNC1_OUT{slash}GPIO1_9-PadE17)") (class "Default")
      (node (ref "U3") (pin "E17") (pinfunction "UART0_RTSN/UART4_TXD/DCAN1_RX/I2C1_SCL/SPI1_D1/SPI1_CS0/PR1_EDC_SYNC1_OUT/GPIO1_9_E17") (pintype "bidirectional+no_connect"))
    )
    (net (code "101") (name "unconnected-(U3B-USB0_CE-PadM15)") (class "Default")
      (node (ref "U3") (pin "M15") (pinfunction "USB0_CE_M15") (pintype "passive+no_connect"))
    )
    (net (code "102") (name "unconnected-(U3B-USB0_DRVVBUS{slash}GPIO0_18-PadF16)") (class "Default")
      (node (ref "U3") (pin "F16") (pinfunction "USB0_DRVVBUS/GPIO0_18_F16") (pintype "passive+no_connect"))
    )
    (net (code "103") (name "unconnected-(U3B-USB1_CE-PadP18)") (class "Default")
      (node (ref "U3") (pin "P18") (pinfunction "USB1_CE_P18") (pintype "passive+no_connect"))
    )
    (net (code "104") (name "unconnected-(U8-NC-Pad5)") (class "Default")
      (node (ref "U8") (pin "5") (pinfunction "NC_5") (pintype "passive+no_connect"))
    )
    (net (code "105") (name "unconnected-(U9-ID-Pad3)") (class "Default")
      (node (ref "U9") (pin "3") (pinfunction "ID_3") (pintype "passive+no_connect"))
    )
    (net (code "106") (name "unconnected-(U9-NC-Pad5)") (class "Default")
      (node (ref "U9") (pin "5") (pinfunction "NC_5") (pintype "passive+no_connect"))
    )
  )
)
